# YOTSUBA__X_EM_ver_1_0.net
KiCad netlist of a schematic drawn in EAGLE
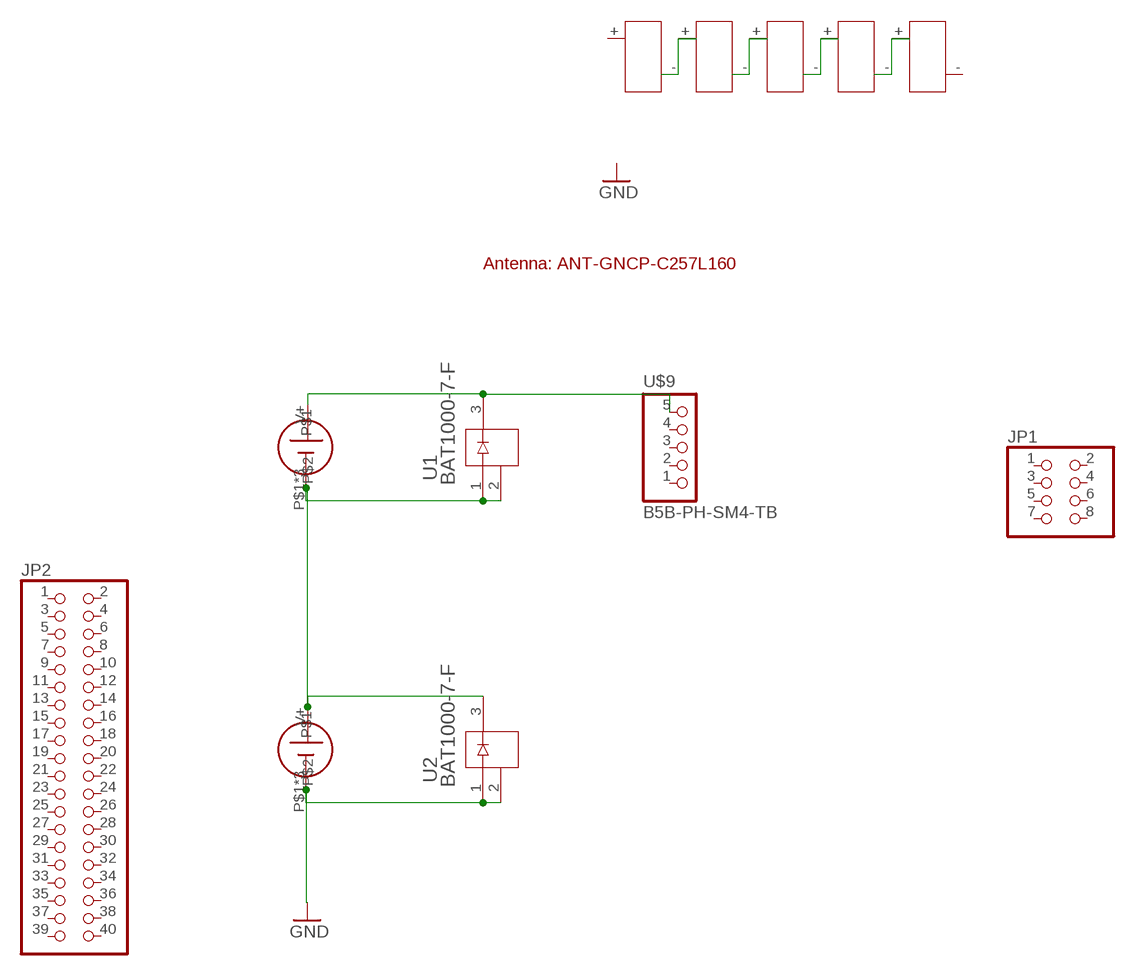
[diagram p0: schematic, sheet 1]

(export (version "E")
  (design (tool "Eeschema 10.0.6"))
  (components
    (comp (ref "JP1")
      (value "PINHD-2X4")
      (footprint "eagle-import:2X04")
      (libsource (lib "eagle-import") (part "PINHD-2X4"))
    )
    (comp (ref "JP2")
      (value "PINHD-2X20")
      (footprint "eagle-import:2X20")
      (libsource (lib "eagle-import") (part "PINHD-2X20"))
    )
    (comp (ref "U$1")
      (value "SOLAR_2.0_SOLAR")
      (footprint "eagle-import:SOLAR_2.0_SOLAR")
      (libsource (lib "eagle-import") (part "SOLAR_2.0_SOLAR"))
    )
    (comp (ref "U$2")
      (value "ANT-GNCP-C257L160")
      (footprint "eagle-import:ANT-GNCP-C257L160")
      (libsource (lib "eagle-import") (part "ANT-GNCP-C257L160"))
    )
    (comp (ref "U$3")
      (value "KSP-F12")
      (footprint "eagle-import:KSP-F12")
      (libsource (lib "eagle-import") (part "KSP-F12"))
    )
    (comp (ref "U$4")
      (value "KSP-F12")
      (footprint "eagle-import:KSP-F12")
      (libsource (lib "eagle-import") (part "KSP-F12"))
    )
    (comp (ref "U$5")
      (value "KSP-F12")
      (footprint "eagle-import:KSP-F12")
      (libsource (lib "eagle-import") (part "KSP-F12"))
    )
    (comp (ref "U$6")
      (value "KSP-F12")
      (footprint "eagle-import:KSP-F12")
      (libsource (lib "eagle-import") (part "KSP-F12"))
    )
    (comp (ref "U$7")
      (value "KSP-F12")
      (footprint "eagle-import:KSP-F12")
      (libsource (lib "eagle-import") (part "KSP-F12"))
    )
    (comp (ref "U$8")
      (value "SOLAR_2.0_SOLAR")
      (footprint "eagle-import:SOLAR_2.0_SOLAR")
      (libsource (lib "eagle-import") (part "SOLAR_2.0_SOLAR"))
    )
    (comp (ref "U$9")
      (value "B5B-PH-SM4-TB")
      (footprint "eagle-import:B5B-PH-SM4-TB")
      (libsource (lib "eagle-import") (part "B5B-PH-SM4-TB"))
    )
    (comp (ref "U1")
      (value "BAT1000-7-F")
      (footprint "eagle-import:SOT23_BAT_DIO")
      (fields (field (name "COPYRIGHT") "Copyright (C) 2022 Ultra Librarian. All rights reserved."))
      (libsource (lib "eagle-import") (part "BAT1000-7-F"))
    )
    (comp (ref "U2")
      (value "BAT1000-7-F")
      (footprint "eagle-import:SOT23_BAT_DIO")
      (fields (field (name "COPYRIGHT") "Copyright (C) 2022 Ultra Librarian. All rights reserved."))
      (libsource (lib "eagle-import") (part "BAT1000-7-F"))
    )
  )
  (nets
    (net (code "1") (name "GND") (class "Default")
      (node (ref "U$8") (pin "P$1") (pinfunction "P$1_P$1") (pintype "bidirectional"))
      (node (ref "U$8") (pin "P$2") (pinfunction "P$1_P$2") (pintype "bidirectional"))
      (node (ref "U$8") (pin "P$3") (pinfunction "P$1_P$3") (pintype "bidirectional"))
      (node (ref "U2") (pin "1") (pinfunction "1_1") (pintype "passive"))
      (node (ref "U2") (pin "2") (pinfunction "2_2") (pintype "passive"))
    )
    (net (code "2") (name "Net-(U$1-P$2)") (class "Default")
      (node (ref "U$1") (pin "V+") (pinfunction "P$2_V+") (pintype "bidirectional"))
      (node (ref "U$9") (pin "5") (pinfunction "5_5") (pintype "passive"))
      (node (ref "U1") (pin "3") (pinfunction "3_3") (pintype "passive"))
    )
    (net (code "3") (name "Net-(U$3-Pad-)") (class "Default")
      (node (ref "U$3") (pin "-") (pinfunction "-_-") (pintype "bidirectional"))
      (node (ref "U$4") (pin "+") (pinfunction "+_+") (pintype "bidirectional"))
    )
    (net (code "4") (name "Net-(U$4-Pad-)") (class "Default")
      (node (ref "U$4") (pin "-") (pinfunction "-_-") (pintype "bidirectional"))
      (node (ref "U$5") (pin "+") (pinfunction "+_+") (pintype "bidirectional"))
    )
    (net (code "5") (name "Net-(U$5-Pad-)") (class "Default")
      (node (ref "U$5") (pin "-") (pinfunction "-_-") (pintype "bidirectional"))
      (node (ref "U$6") (pin "+") (pinfunction "+_+") (pintype "bidirectional"))
    )
    (net (code "6") (name "Net-(U$6-Pad-)") (class "Default")
      (node (ref "U$6") (pin "-") (pinfunction "-_-") (pintype "bidirectional"))
      (node (ref "U$7") (pin "+") (pinfunction "+_+") (pintype "bidirectional"))
    )
    (net (code "7") (name "Net-(U$8-P$2)") (class "Default")
      (node (ref "U$1") (pin "P$1") (pinfunction "P$1_P$1") (pintype "bidirectional"))
      (node (ref "U$1") (pin "P$2") (pinfunction "P$1_P$2") (pintype "bidirectional"))
      (node (ref "U$1") (pin "P$3") (pinfunction "P$1_P$3") (pintype "bidirectional"))
      (node (ref "U$8") (pin "V+") (pinfunction "P$2_V+") (pintype "bidirectional"))
      (node (ref "U1") (pin "1") (pinfunction "1_1") (pintype "passive"))
      (node (ref "U1") (pin "2") (pinfunction "2_2") (pintype "passive"))
      (node (ref "U2") (pin "3") (pinfunction "3_3") (pintype "passive"))
    )
    (net (code "8") (name "unconnected-(JP1-Pad1)") (class "Default")
      (node (ref "JP1") (pin "1") (pinfunction "1_1") (pintype "passive"))
    )
    (net (code "9") (name "unconnected-(JP1-Pad2)") (class "Default")
      (node (ref "JP1") (pin "2") (pinfunction "2_2") (pintype "passive"))
    )
    (net (code "10") (name "unconnected-(JP1-Pad3)") (class "Default")
      (node (ref "JP1") (pin "3") (pinfunction "3_3") (pintype "passive"))
    )
    (net (code "11") (name "unconnected-(JP1-Pad4)") (class "Default")
      (node (ref "JP1") (pin "4") (pinfunction "4_4") (pintype "passive"))
    )
    (net (code "12") (name "unconnected-(JP1-Pad5)") (class "Default")
      (node (ref "JP1") (pin "5") (pinfunction "5_5") (pintype "passive"))
    )
    (net (code "13") (name "unconnected-(JP1-Pad6)") (class "Default")
      (node (ref "JP1") (pin "6") (pinfunction "6_6") (pintype "passive"))
    )
    (net (code "14") (name "unconnected-(JP1-Pad7)") (class "Default")
      (node (ref "JP1") (pin "7") (pinfunction "7_7") (pintype "passive"))
    )
    (net (code "15") (name "unconnected-(JP1-Pad8)") (class "Default")
      (node (ref "JP1") (pin "8") (pinfunction "8_8") (pintype "passive"))
    )
    (net (code "16") (name "unconnected-(JP2-Pad1)") (class "Default")
      (node (ref "JP2") (pin "1") (pinfunction "1_1") (pintype "passive"))
    )
    (net (code "17") (name "unconnected-(JP2-Pad2)") (class "Default")
      (node (ref "JP2") (pin "2") (pinfunction "2_2") (pintype "passive"))
    )
    (net (code "18") (name "unconnected-(JP2-Pad3)") (class "Default")
      (node (ref "JP2") (pin "3") (pinfunction "3_3") (pintype "passive"))
    )
    (net (code "19") (name "unconnected-(JP2-Pad4)") (class "Default")
      (node (ref "JP2") (pin "4") (pinfunction "4_4") (pintype "passive"))
    )
    (net (code "20") (name "unconnected-(JP2-Pad5)") (class "Default")
      (node (ref "JP2") (pin "5") (pinfunction "5_5") (pintype "passive"))
    )
    (net (code "21") (name "unconnected-(JP2-Pad6)") (class "Default")
      (node (ref "JP2") (pin "6") (pinfunction "6_6") (pintype "passive"))
    )
    (net (code "22") (name "unconnected-(JP2-Pad7)") (class "Default")
      (node (ref "JP2") (pin "7") (pinfunction "7_7") (pintype "passive"))
    )
    (net (code "23") (name "unconnected-(JP2-Pad8)") (class "Default")
      (node (ref "JP2") (pin "8") (pinfunction "8_8") (pintype "passive"))
    )
    (net (code "24") (name "unconnected-(JP2-Pad9)") (class "Default")
      (node (ref "JP2") (pin "9") (pinfunction "9_9") (pintype "passive"))
    )
    (net (code "25") (name "unconnected-(JP2-Pad10)") (class "Default")
      (node (ref "JP2") (pin "10") (pinfunction "10_10") (pintype "passive"))
    )
    (net (code "26") (name "unconnected-(JP2-Pad11)") (class "Default")
      (node (ref "JP2") (pin "11") (pinfunction "11_11") (pintype "passive"))
    )
    (net (code "27") (name "unconnected-(JP2-Pad12)") (class "Default")
      (node (ref "JP2") (pin "12") (pinfunction "12_12") (pintype "passive"))
    )
    (net (code "28") (name "unconnected-(JP2-Pad13)") (class "Default")
      (node (ref "JP2") (pin "13") (pinfunction "13_13") (pintype "passive"))
    )
    (net (code "29") (name "unconnected-(JP2-Pad14)") (class "Default")
      (node (ref "JP2") (pin "14") (pinfunction "14_14") (pintype "passive"))
    )
    (net (code "30") (name "unconnected-(JP2-Pad15)") (class "Default")
      (node (ref "JP2") (pin "15") (pinfunction "15_15") (pintype "passive"))
    )
    (net (code "31") (name "unconnected-(JP2-Pad16)") (class "Default")
      (node (ref "JP2") (pin "16") (pinfunction "16_16") (pintype "passive"))
    )
    (net (code "32") (name "unconnected-(JP2-Pad17)") (class "Default")
      (node (ref "JP2") (pin "17") (pinfunction "17_17") (pintype "passive"))
    )
    (net (code "33") (name "unconnected-(JP2-Pad18)") (class "Default")
      (node (ref "JP2") (pin "18") (pinfunction "18_18") (pintype "passive"))
    )
    (net (code "34") (name "unconnected-(JP2-Pad19)") (class "Default")
      (node (ref "JP2") (pin "19") (pinfunction "19_19") (pintype "passive"))
    )
    (net (code "35") (name "unconnected-(JP2-Pad20)") (class "Default")
      (node (ref "JP2") (pin "20") (pinfunction "20_20") (pintype "passive"))
    )
    (net (code "36") (name "unconnected-(JP2-Pad21)") (class "Default")
      (node (ref "JP2") (pin "21") (pinfunction "21_21") (pintype "passive"))
    )
    (net (code "37") (name "unconnected-(JP2-Pad22)") (class "Default")
      (node (ref "JP2") (pin "22") (pinfunction "22_22") (pintype "passive"))
    )
    (net (code "38") (name "unconnected-(JP2-Pad23)") (class "Default")
      (node (ref "JP2") (pin "23") (pinfunction "23_23") (pintype "passive"))
    )
    (net (code "39") (name "unconnected-(JP2-Pad24)") (class "Default")
      (node (ref "JP2") (pin "24") (pinfunction "24_24") (pintype "passive"))
    )
    (net (code "40") (name "unconnected-(JP2-Pad25)") (class "Default")
      (node (ref "JP2") (pin "25") (pinfunction "25_25") (pintype "passive"))
    )
    (net (code "41") (name "unconnected-(JP2-Pad26)") (class "Default")
      (node (ref "JP2") (pin "26") (pinfunction "26_26") (pintype "passive"))
    )
    (net (code "42") (name "unconnected-(JP2-Pad27)") (class "Default")
      (node (ref "JP2") (pin "27") (pinfunction "27_27") (pintype "passive"))
    )
    (net (code "43") (name "unconnected-(JP2-Pad28)") (class "Default")
      (node (ref "JP2") (pin "28") (pinfunction "28_28") (pintype "passive"))
    )
    (net (code "44") (name "unconnected-(JP2-Pad29)") (class "Default")
      (node (ref "JP2") (pin "29") (pinfunction "29_29") (pintype "passive"))
    )
    (net (code "45") (name "unconnected-(JP2-Pad30)") (class "Default")
      (node (ref "JP2") (pin "30") (pinfunction "30_30") (pintype "passive"))
    )
    (net (code "46") (name "unconnected-(JP2-Pad31)") (class "Default")
      (node (ref "JP2") (pin "31") (pinfunction "31_31") (pintype "passive"))
    )
    (net (code "47") (name "unconnected-(JP2-Pad32)") (class "Default")
      (node (ref "JP2") (pin "32") (pinfunction "32_32") (pintype "passive"))
    )
    (net (code "48") (name "unconnected-(JP2-Pad33)") (class "Default")
      (node (ref "JP2") (pin "33") (pinfunction "33_33") (pintype "passive"))
    )
    (net (code "49") (name "unconnected-(JP2-Pad34)") (class "Default")
      (node (ref "JP2") (pin "34") (pinfunction "34_34") (pintype "passive"))
    )
    (net (code "50") (name "unconnected-(JP2-Pad35)") (class "Default")
      (node (ref "JP2") (pin "35") (pinfunction "35_35") (pintype "passive"))
    )
    (net (code "51") (name "unconnected-(JP2-Pad36)") (class "Default")
      (node (ref "JP2") (pin "36") (pinfunction "36_36") (pintype "passive"))
    )
    (net (code "52") (name "unconnected-(JP2-Pad37)") (class "Default")
      (node (ref "JP2") (pin "37") (pinfunction "37_37") (pintype "passive"))
    )
    (net (code "53") (name "unconnected-(JP2-Pad38)") (class "Default")
      (node (ref "JP2") (pin "38") (pinfunction "38_38") (pintype "passive"))
    )
    (net (code "54") (name "unconnected-(JP2-Pad39)") (class "Default")
      (node (ref "JP2") (pin "39") (pinfunction "39_39") (pintype "passive"))
    )
    (net (code "55") (name "unconnected-(JP2-Pad40)") (class "Default")
      (node (ref "JP2") (pin "40") (pinfunction "40_40") (pintype "passive"))
    )
    (net (code "56") (name "unconnected-(U$3-Pad+)") (class "Default")
      (node (ref "U$3") (pin "+") (pinfunction "+_+") (pintype "bidirectional"))
    )
    (net (code "57") (name "unconnected-(U$7-Pad-)") (class "Default")
      (node (ref "U$7") (pin "-") (pinfunction "-_-") (pintype "bidirectional"))
    )
    (net (code "58") (name "unconnected-(U$9-Pad1)") (class "Default")
      (node (ref "U$9") (pin "1") (pinfunction "1_1") (pintype "passive"))
    )
    (net (code "59") (name "unconnected-(U$9-Pad2)") (class "Default")
      (node (ref "U$9") (pin "2") (pinfunction "2_2") (pintype "passive"))
    )
    (net (code "60") (name "unconnected-(U$9-Pad3)") (class "Default")
      (node (ref "U$9") (pin "3") (pinfunction "3_3") (pintype "passive"))
    )
    (net (code "61") (name "unconnected-(U$9-Pad4)") (class "Default")
      (node (ref "U$9") (pin "4") (pinfunction "4_4") (pintype "passive"))
    )
  )
)
